# C172-XPNDR-sh_matics.net
KiCad netlist of a schematic drawn in EasyEDA
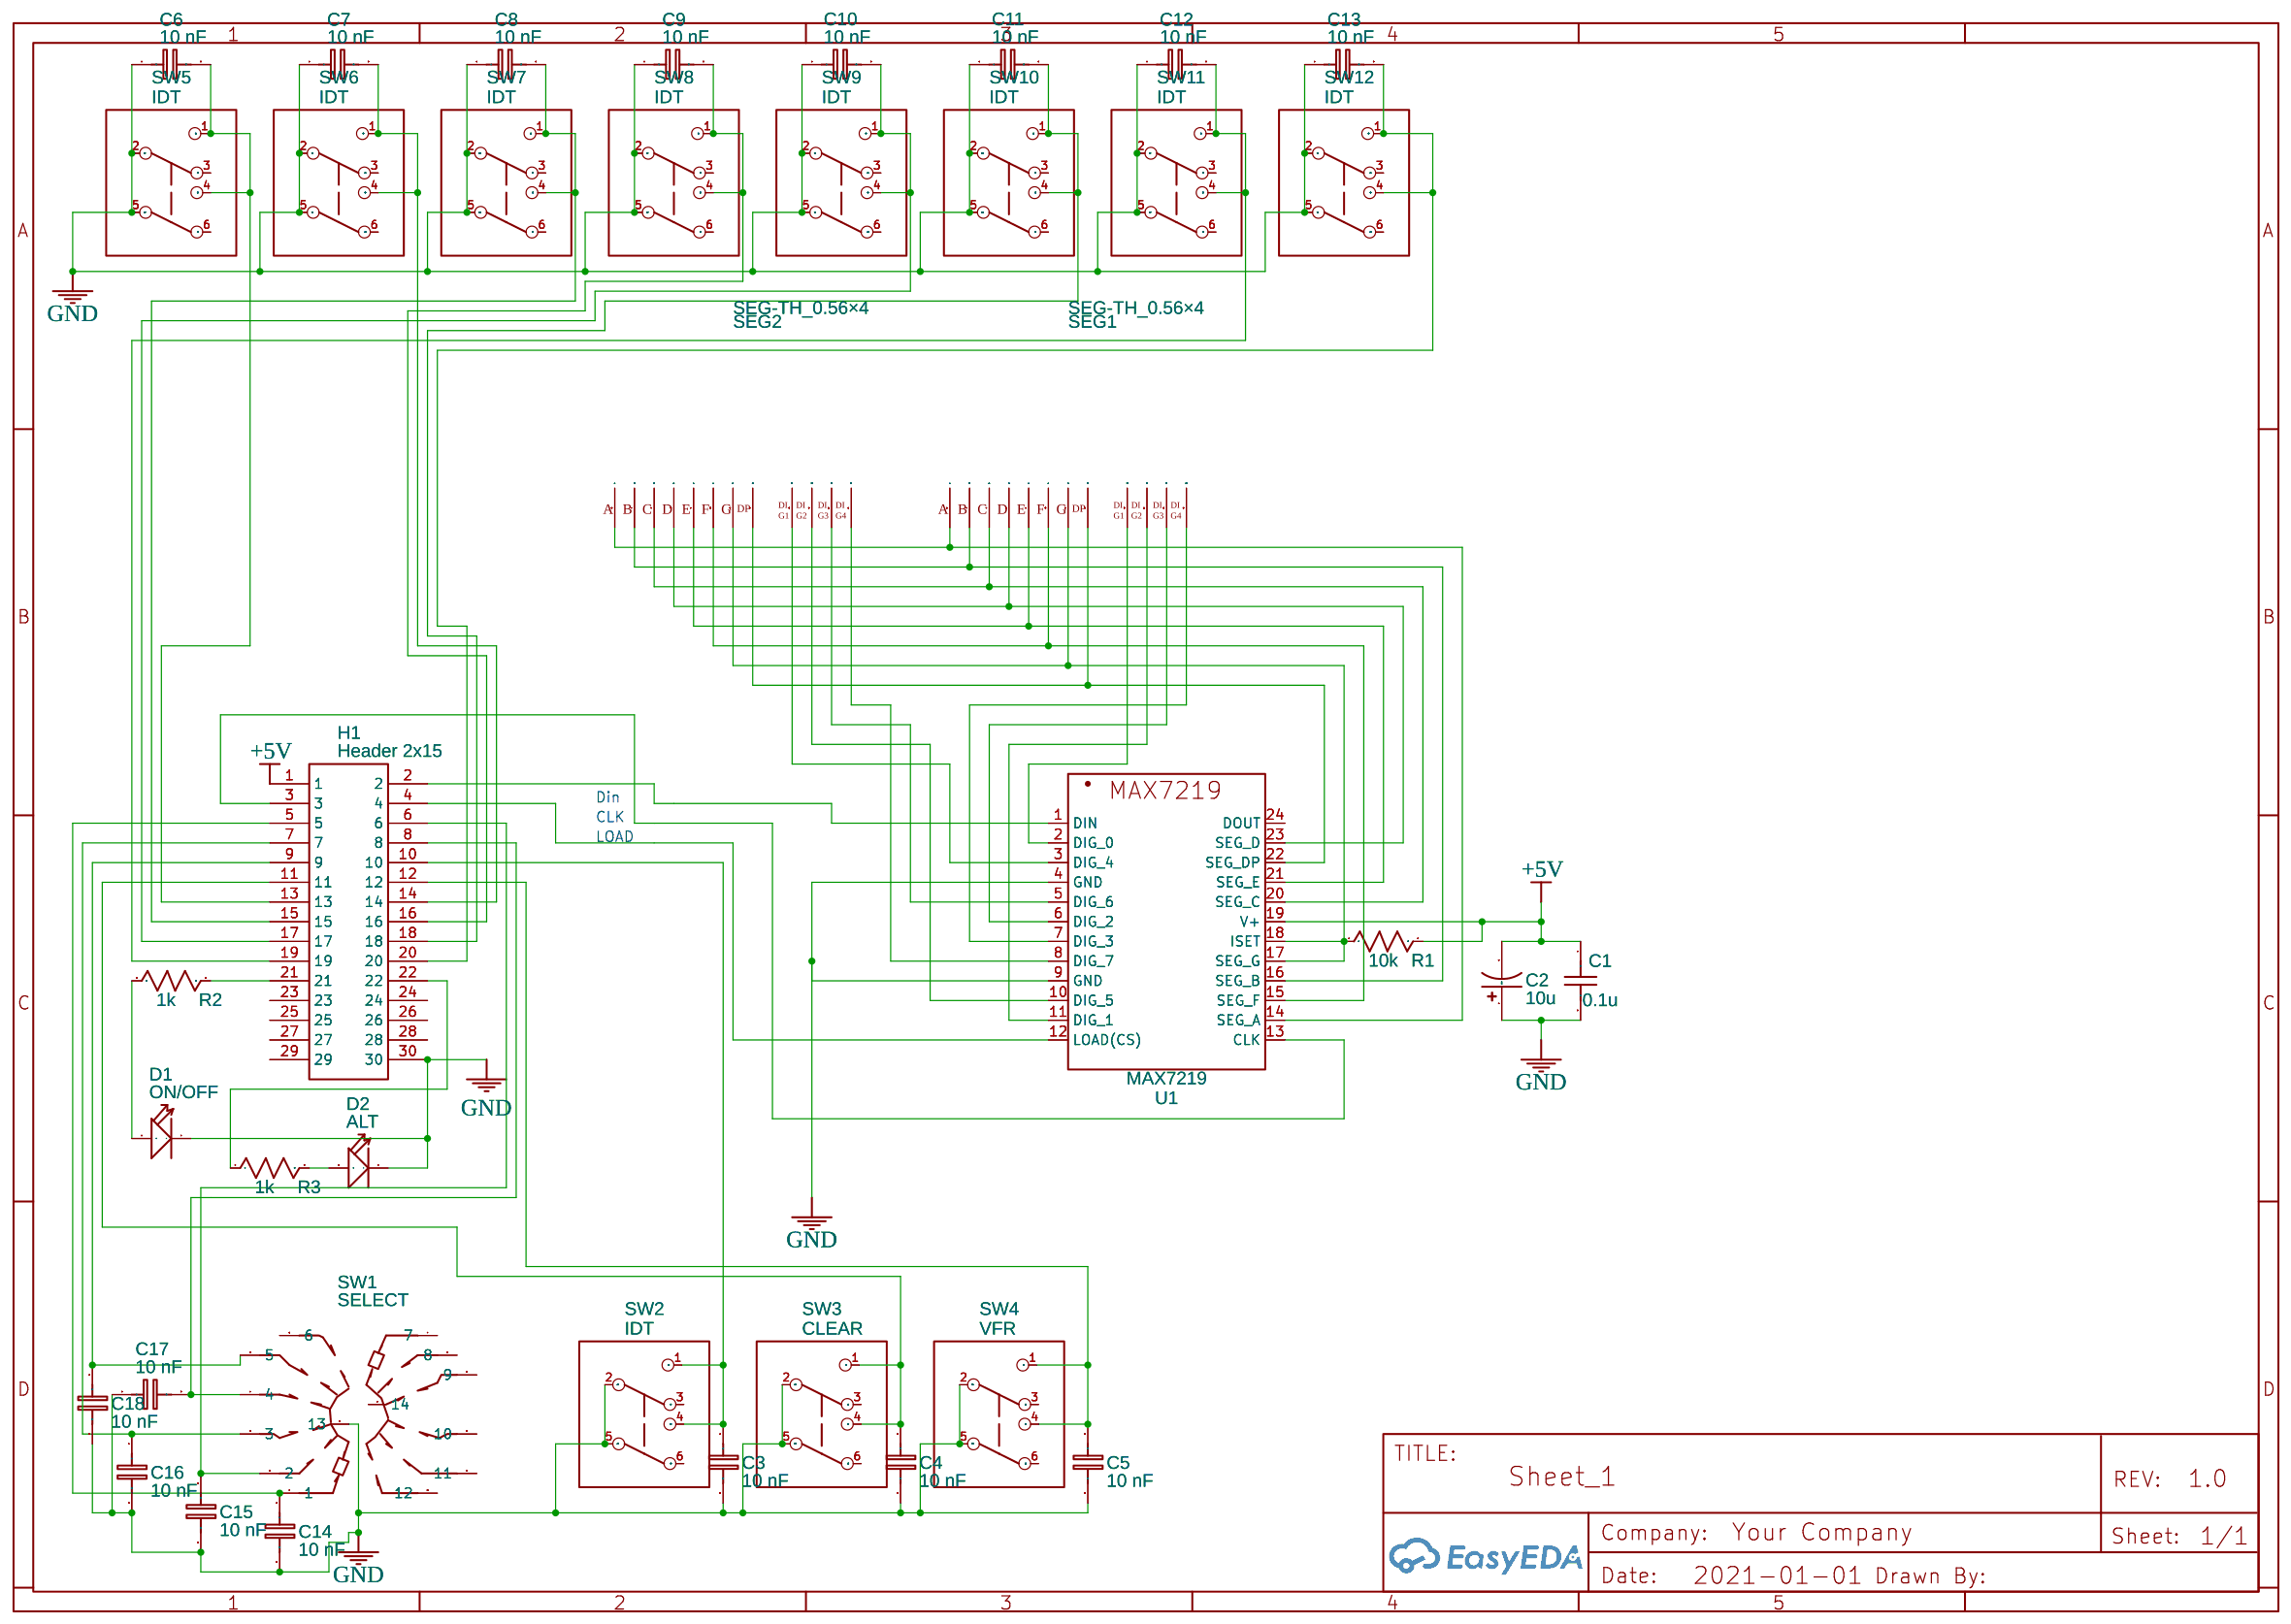
[diagram p0: schematic sheet]

(export (version "E")
  (design (tool "Eeschema 10.0.6"))
  (components
    (comp (ref "C1") (value "0.1u") (libsource (lib "") (part "C_0201_US")))
    (comp (ref "C2") (value "10u") (libsource (lib "") (part "C_Tan_SMD_A_US")))
    (comp (ref "C3") (value "10 nF") (libsource (lib "") (part "Capacitor1_EU_2")))
    (comp (ref "C4") (value "10 nF") (libsource (lib "") (part "Capacitor1_EU_2")))
    (comp (ref "C5") (value "10 nF") (libsource (lib "") (part "Capacitor1_EU_1")))
    (comp (ref "C6") (value "10 nF") (libsource (lib "") (part "Capacitor1_EU")))
    (comp (ref "C7") (value "10 nF") (libsource (lib "") (part "Capacitor1_EU_3")))
    (comp (ref "C8") (value "10 nF") (libsource (lib "") (part "Capacitor1_EU_3")))
    (comp (ref "C9") (value "10 nF") (libsource (lib "") (part "Capacitor1_EU_3")))
    (comp (ref "C10") (value "10 nF") (libsource (lib "") (part "Capacitor1_EU_3")))
    (comp (ref "C11") (value "10 nF") (libsource (lib "") (part "Capacitor1_EU_3")))
    (comp (ref "C12") (value "10 nF") (libsource (lib "") (part "Capacitor1_EU")))
    (comp (ref "C13") (value "10 nF") (libsource (lib "") (part "Capacitor1_EU")))
    (comp (ref "C14") (value "10 nF") (libsource (lib "") (part "Capacitor1_EU_1")))
    (comp (ref "C15") (value "10 nF") (libsource (lib "") (part "Capacitor1_EU_1")))
    (comp (ref "C16") (value "10 nF") (libsource (lib "") (part "Capacitor1_EU_1")))
    (comp (ref "C17") (value "10 nF") (libsource (lib "") (part "Capacitor1_EU")))
    (comp (ref "C18") (value "10 nF") (libsource (lib "") (part "Capacitor1_EU_1")))
    (comp (ref "D1")
      (value "ON/OFF")
      (fields (field (name "BOM_Manufacturer Part") "?"))
      (libsource (lib "") (part "DIP LED Red-Red;"))
    )
    (comp (ref "D2")
      (value "ALT")
      (fields (field (name "BOM_Manufacturer Part") "?"))
      (libsource (lib "") (part "DIP LED Red-Red;"))
    )
    (comp (ref "H1") (value "Header 2x15") (libsource (lib "") (part "Header 2x15")))
    (comp (ref "R1") (value "10k") (libsource (lib "") (part "R_0201_US")))
    (comp (ref "R2") (value "1k") (libsource (lib "") (part "R_0201_US")))
    (comp (ref "R3") (value "1k") (libsource (lib "") (part "R_0201_US")))
    (comp (ref "SEG1")
      (value "SEG-TH_0.56×4")
      (fields (field (name "BOM_Supplier Part") "C109200"))
      (libsource (lib "") (part "SEG-TH_0.56×4"))
    )
    (comp (ref "SEG2")
      (value "SEG-TH_0.56×4")
      (fields (field (name "BOM_Supplier Part") "C109200"))
      (libsource (lib "") (part "SEG-TH_0.56×4"))
    )
    (comp (ref "SW1")
      (value "SELECT")
      (fields (field (name "BOM_Manufacturer Part") "CK1060"))
      (libsource (lib "") (part "LORLIN  2P6T PCB SW"))
    )
    (comp (ref "SW2") (value "IDT") (libsource (lib "") (part "SW_PUSH_DPDT_MINI_7x7")))
    (comp (ref "SW3") (value "CLEAR") (libsource (lib "") (part "SW_PUSH_DPDT_MINI_7x7")))
    (comp (ref "SW4") (value "VFR") (libsource (lib "") (part "SW_PUSH_DPDT_MINI_7x7")))
    (comp (ref "SW5") (value "IDT") (libsource (lib "") (part "SW_PUSH_DPDT_MINI_7x7")))
    (comp (ref "SW6") (value "IDT") (libsource (lib "") (part "SW_PUSH_DPDT_MINI_7x7")))
    (comp (ref "SW7") (value "IDT") (libsource (lib "") (part "SW_PUSH_DPDT_MINI_7x7")))
    (comp (ref "SW8") (value "IDT") (libsource (lib "") (part "SW_PUSH_DPDT_MINI_7x7")))
    (comp (ref "SW9") (value "IDT") (libsource (lib "") (part "SW_PUSH_DPDT_MINI_7x7")))
    (comp (ref "SW10") (value "IDT") (libsource (lib "") (part "SW_PUSH_DPDT_MINI_7x7")))
    (comp (ref "SW11") (value "IDT") (libsource (lib "") (part "SW_PUSH_DPDT_MINI_7x7")))
    (comp (ref "SW12") (value "IDT") (libsource (lib "") (part "SW_PUSH_DPDT_MINI_7x7")))
    (comp (ref "U1")
      (value "MAX7219")
      (fields (field (name "BOM_Manufacturer Part") "MAXIM") (field (name "BOM_Supplier Part") "C129565"))
      (libsource (lib "") (part "MAX7219"))
    )
  )
  (nets
    (net (code "1") (name "+5V") (class "Default")
      (node (ref "C1") (pin "1") (pinfunction "1_1") (pintype "unspecified"))
      (node (ref "C2") (pin "2") (pinfunction "2_2") (pintype "unspecified"))
      (node (ref "H1") (pin "1") (pinfunction "1_1") (pintype "unspecified"))
      (node (ref "R1") (pin "2") (pinfunction "2_2") (pintype "unspecified"))
      (node (ref "U1") (pin "19") (pinfunction "V+_19") (pintype "unspecified"))
    )
    (net (code "2") (name "GND") (class "Default")
      (node (ref "C1") (pin "2") (pinfunction "2_2") (pintype "unspecified"))
      (node (ref "C10") (pin "1") (pinfunction "1_1") (pintype "unspecified"))
      (node (ref "C11") (pin "1") (pinfunction "1_1") (pintype "unspecified"))
      (node (ref "C12") (pin "1") (pinfunction "1_1") (pintype "unspecified"))
      (node (ref "C13") (pin "1") (pinfunction "1_1") (pintype "unspecified"))
      (node (ref "C14") (pin "2") (pinfunction "2_2") (pintype "unspecified"))
      (node (ref "C15") (pin "2") (pinfunction "2_2") (pintype "unspecified"))
      (node (ref "C16") (pin "2") (pinfunction "2_2") (pintype "unspecified"))
      (node (ref "C17") (pin "1") (pinfunction "1_1") (pintype "unspecified"))
      (node (ref "C18") (pin "2") (pinfunction "2_2") (pintype "unspecified"))
      (node (ref "C2") (pin "1") (pinfunction "1_1") (pintype "unspecified"))
      (node (ref "C3") (pin "2") (pinfunction "2_2") (pintype "unspecified"))
      (node (ref "C4") (pin "2") (pinfunction "2_2") (pintype "unspecified"))
      (node (ref "C5") (pin "2") (pinfunction "2_2") (pintype "unspecified"))
      (node (ref "C6") (pin "1") (pinfunction "1_1") (pintype "unspecified"))
      (node (ref "C7") (pin "1") (pinfunction "1_1") (pintype "unspecified"))
      (node (ref "C8") (pin "1") (pinfunction "1_1") (pintype "unspecified"))
      (node (ref "C9") (pin "1") (pinfunction "1_1") (pintype "unspecified"))
      (node (ref "D1") (pin "K") (pinfunction "-_K") (pintype "unspecified"))
      (node (ref "D2") (pin "K") (pinfunction "-_K") (pintype "unspecified"))
      (node (ref "H1") (pin "30") (pinfunction "30_30") (pintype "unspecified"))
      (node (ref "SW1") (pin "13") (pinfunction "13_13") (pintype "unspecified"))
      (node (ref "SW10") (pin "2") (pinfunction "COM1_2") (pintype "unspecified"))
      (node (ref "SW10") (pin "5") (pinfunction "COM2_5") (pintype "unspecified"))
      (node (ref "SW11") (pin "2") (pinfunction "COM1_2") (pintype "unspecified"))
      (node (ref "SW11") (pin "5") (pinfunction "COM2_5") (pintype "unspecified"))
      (node (ref "SW12") (pin "2") (pinfunction "COM1_2") (pintype "unspecified"))
      (node (ref "SW12") (pin "5") (pinfunction "COM2_5") (pintype "unspecified"))
      (node (ref "SW2") (pin "2") (pinfunction "COM1_2") (pintype "unspecified"))
      (node (ref "SW2") (pin "5") (pinfunction "COM2_5") (pintype "unspecified"))
      (node (ref "SW3") (pin "2") (pinfunction "COM1_2") (pintype "unspecified"))
      (node (ref "SW3") (pin "5") (pinfunction "COM2_5") (pintype "unspecified"))
      (node (ref "SW4") (pin "2") (pinfunction "COM1_2") (pintype "unspecified"))
      (node (ref "SW4") (pin "5") (pinfunction "COM2_5") (pintype "unspecified"))
      (node (ref "SW5") (pin "2") (pinfunction "COM1_2") (pintype "unspecified"))
      (node (ref "SW5") (pin "5") (pinfunction "COM2_5") (pintype "unspecified"))
      (node (ref "SW6") (pin "2") (pinfunction "COM1_2") (pintype "unspecified"))
      (node (ref "SW6") (pin "5") (pinfunction "COM2_5") (pintype "unspecified"))
      (node (ref "SW7") (pin "2") (pinfunction "COM1_2") (pintype "unspecified"))
      (node (ref "SW7") (pin "5") (pinfunction "COM2_5") (pintype "unspecified"))
      (node (ref "SW8") (pin "2") (pinfunction "COM1_2") (pintype "unspecified"))
      (node (ref "SW8") (pin "5") (pinfunction "COM2_5") (pintype "unspecified"))
      (node (ref "SW9") (pin "2") (pinfunction "COM1_2") (pintype "unspecified"))
      (node (ref "SW9") (pin "5") (pinfunction "COM2_5") (pintype "unspecified"))
      (node (ref "U1") (pin "4") (pinfunction "GND_4") (pintype "unspecified"))
      (node (ref "U1") (pin "9") (pinfunction "GND_9") (pintype "unspecified"))
    )
    (net (code "3") (name "Net-(C14-Pad1)") (class "Default")
      (node (ref "C14") (pin "1") (pinfunction "1_1") (pintype "unspecified"))
      (node (ref "H1") (pin "5") (pinfunction "5_5") (pintype "unspecified"))
      (node (ref "SW1") (pin "1") (pinfunction "1_1") (pintype "unspecified"))
    )
    (net (code "4") (name "Net-(C15-Pad1)") (class "Default")
      (node (ref "C15") (pin "1") (pinfunction "1_1") (pintype "unspecified"))
      (node (ref "H1") (pin "6") (pinfunction "6_6") (pintype "unspecified"))
      (node (ref "SW1") (pin "2") (pinfunction "2_2") (pintype "unspecified"))
    )
    (net (code "5") (name "Net-(C16-Pad1)") (class "Default")
      (node (ref "C16") (pin "1") (pinfunction "1_1") (pintype "unspecified"))
      (node (ref "H1") (pin "7") (pinfunction "7_7") (pintype "unspecified"))
      (node (ref "SW1") (pin "3") (pinfunction "3_3") (pintype "unspecified"))
    )
    (net (code "6") (name "Net-(C17-Pad2)") (class "Default")
      (node (ref "C17") (pin "2") (pinfunction "2_2") (pintype "unspecified"))
      (node (ref "H1") (pin "8") (pinfunction "8_8") (pintype "unspecified"))
      (node (ref "SW1") (pin "4") (pinfunction "4_4") (pintype "unspecified"))
    )
    (net (code "7") (name "Net-(C18-Pad1)") (class "Default")
      (node (ref "C18") (pin "1") (pinfunction "1_1") (pintype "unspecified"))
      (node (ref "H1") (pin "9") (pinfunction "9_9") (pintype "unspecified"))
      (node (ref "SW1") (pin "5") (pinfunction "5_5") (pintype "unspecified"))
    )
    (net (code "8") (name "Net-(D1-+)") (class "Default")
      (node (ref "D1") (pin "A") (pinfunction "+_A") (pintype "unspecified"))
      (node (ref "R2") (pin "1") (pinfunction "1_1") (pintype "unspecified"))
    )
    (net (code "9") (name "Net-(D2-+)") (class "Default")
      (node (ref "D2") (pin "A") (pinfunction "+_A") (pintype "unspecified"))
      (node (ref "R3") (pin "2") (pinfunction "2_2") (pintype "unspecified"))
    )
    (net (code "10") (name "Net-(H1-Pad21)") (class "Default")
      (node (ref "H1") (pin "21") (pinfunction "21_21") (pintype "unspecified"))
      (node (ref "R2") (pin "2") (pinfunction "2_2") (pintype "unspecified"))
    )
    (net (code "11") (name "Net-(H1-Pad22)") (class "Default")
      (node (ref "H1") (pin "22") (pinfunction "22_22") (pintype "unspecified"))
      (node (ref "R3") (pin "1") (pinfunction "1_1") (pintype "unspecified"))
    )
    (net (code "12") (name "Net-(SEG1-A)") (class "Default")
      (node (ref "SEG1") (pin "11") (pinfunction "A_11") (pintype "input"))
      (node (ref "SEG2") (pin "11") (pinfunction "A_11") (pintype "input"))
      (node (ref "U1") (pin "14") (pinfunction "SEG_A_14") (pintype "unspecified"))
    )
    (net (code "13") (name "Net-(SEG1-B)") (class "Default")
      (node (ref "SEG1") (pin "7") (pinfunction "B_7") (pintype "input"))
      (node (ref "SEG2") (pin "7") (pinfunction "B_7") (pintype "input"))
      (node (ref "U1") (pin "16") (pinfunction "SEG_B_16") (pintype "unspecified"))
    )
    (net (code "14") (name "Net-(SEG1-C)") (class "Default")
      (node (ref "SEG1") (pin "4") (pinfunction "C_4") (pintype "input"))
      (node (ref "SEG2") (pin "4") (pinfunction "C_4") (pintype "input"))
      (node (ref "U1") (pin "20") (pinfunction "SEG_C_20") (pintype "unspecified"))
    )
    (net (code "15") (name "Net-(SEG1-D)") (class "Default")
      (node (ref "SEG1") (pin "2") (pinfunction "D_2") (pintype "input"))
      (node (ref "SEG2") (pin "2") (pinfunction "D_2") (pintype "input"))
      (node (ref "U1") (pin "23") (pinfunction "SEG_D_23") (pintype "unspecified"))
    )
    (net (code "16") (name "Net-(SEG1-DIG1)") (class "Default")
      (node (ref "SEG1") (pin "12") (pinfunction "DIG1_12") (pintype "input"))
      (node (ref "U1") (pin "2") (pinfunction "DIG_0_2") (pintype "unspecified"))
    )
    (net (code "17") (name "Net-(SEG1-DIG2)") (class "Default")
      (node (ref "SEG1") (pin "9") (pinfunction "DIG2_9") (pintype "input"))
      (node (ref "U1") (pin "11") (pinfunction "DIG_1_11") (pintype "unspecified"))
    )
    (net (code "18") (name "Net-(SEG1-DIG3)") (class "Default")
      (node (ref "SEG1") (pin "8") (pinfunction "DIG3_8") (pintype "input"))
      (node (ref "U1") (pin "6") (pinfunction "DIG_2_6") (pintype "unspecified"))
    )
    (net (code "19") (name "Net-(SEG1-DIG4)") (class "Default")
      (node (ref "SEG1") (pin "6") (pinfunction "DIG4_6") (pintype "input"))
      (node (ref "U1") (pin "7") (pinfunction "DIG_3_7") (pintype "unspecified"))
    )
    (net (code "20") (name "Net-(SEG1-DP)") (class "Default")
      (node (ref "SEG1") (pin "3") (pinfunction "DP_3") (pintype "input"))
      (node (ref "SEG2") (pin "3") (pinfunction "DP_3") (pintype "input"))
      (node (ref "U1") (pin "22") (pinfunction "SEG_DP_22") (pintype "unspecified"))
    )
    (net (code "21") (name "Net-(SEG1-E)") (class "Default")
      (node (ref "SEG1") (pin "1") (pinfunction "E_1") (pintype "input"))
      (node (ref "SEG2") (pin "1") (pinfunction "E_1") (pintype "input"))
      (node (ref "U1") (pin "21") (pinfunction "SEG_E_21") (pintype "unspecified"))
    )
    (net (code "22") (name "Net-(SEG1-F)") (class "Default")
      (node (ref "SEG1") (pin "10") (pinfunction "F_10") (pintype "input"))
      (node (ref "SEG2") (pin "10") (pinfunction "F_10") (pintype "input"))
      (node (ref "U1") (pin "15") (pinfunction "SEG_F_15") (pintype "unspecified"))
    )
    (net (code "23") (name "Net-(SEG1-G)") (class "Default")
      (node (ref "R1") (pin "1") (pinfunction "1_1") (pintype "unspecified"))
      (node (ref "SEG1") (pin "5") (pinfunction "G_5") (pintype "input"))
      (node (ref "SEG2") (pin "5") (pinfunction "G_5") (pintype "input"))
      (node (ref "U1") (pin "17") (pinfunction "SEG_G_17") (pintype "unspecified"))
      (node (ref "U1") (pin "18") (pinfunction "ISET_18") (pintype "unspecified"))
    )
    (net (code "24") (name "Net-(SEG2-DIG1)") (class "Default")
      (node (ref "SEG2") (pin "12") (pinfunction "DIG1_12") (pintype "input"))
      (node (ref "U1") (pin "3") (pinfunction "DIG_4_3") (pintype "unspecified"))
    )
    (net (code "25") (name "Net-(SEG2-DIG2)") (class "Default")
      (node (ref "SEG2") (pin "9") (pinfunction "DIG2_9") (pintype "input"))
      (node (ref "U1") (pin "10") (pinfunction "DIG_5_10") (pintype "unspecified"))
    )
    (net (code "26") (name "Net-(SEG2-DIG3)") (class "Default")
      (node (ref "SEG2") (pin "8") (pinfunction "DIG3_8") (pintype "input"))
      (node (ref "U1") (pin "5") (pinfunction "DIG_6_5") (pintype "unspecified"))
    )
    (net (code "27") (name "Net-(SEG2-DIG4)") (class "Default")
      (node (ref "SEG2") (pin "6") (pinfunction "DIG4_6") (pintype "input"))
      (node (ref "U1") (pin "8") (pinfunction "DIG_7_8") (pintype "unspecified"))
    )
    (net (code "28") (name "Net-(SW2-NO1)") (class "Default")
      (node (ref "C3") (pin "1") (pinfunction "1_1") (pintype "unspecified"))
      (node (ref "H1") (pin "10") (pinfunction "10_10") (pintype "unspecified"))
      (node (ref "SW2") (pin "1") (pinfunction "NO1_1") (pintype "unspecified"))
      (node (ref "SW2") (pin "4") (pinfunction "NO2_4") (pintype "unspecified"))
    )
    (net (code "29") (name "Net-(SW3-NO1)") (class "Default")
      (node (ref "C4") (pin "1") (pinfunction "1_1") (pintype "unspecified"))
      (node (ref "H1") (pin "11") (pinfunction "11_11") (pintype "unspecified"))
      (node (ref "SW3") (pin "1") (pinfunction "NO1_1") (pintype "unspecified"))
      (node (ref "SW3") (pin "4") (pinfunction "NO2_4") (pintype "unspecified"))
    )
    (net (code "30") (name "Net-(SW4-NO1)") (class "Default")
      (node (ref "C5") (pin "1") (pinfunction "1_1") (pintype "unspecified"))
      (node (ref "H1") (pin "12") (pinfunction "12_12") (pintype "unspecified"))
      (node (ref "SW4") (pin "1") (pinfunction "NO1_1") (pintype "unspecified"))
      (node (ref "SW4") (pin "4") (pinfunction "NO2_4") (pintype "unspecified"))
    )
    (net (code "31") (name "Net-(SW5-NO1)") (class "Default")
      (node (ref "C6") (pin "2") (pinfunction "2_2") (pintype "unspecified"))
      (node (ref "H1") (pin "13") (pinfunction "13_13") (pintype "unspecified"))
      (node (ref "SW5") (pin "1") (pinfunction "NO1_1") (pintype "unspecified"))
      (node (ref "SW5") (pin "4") (pinfunction "NO2_4") (pintype "unspecified"))
    )
    (net (code "32") (name "Net-(SW6-NO1)") (class "Default")
      (node (ref "C7") (pin "2") (pinfunction "2_2") (pintype "unspecified"))
      (node (ref "H1") (pin "14") (pinfunction "14_14") (pintype "unspecified"))
      (node (ref "SW6") (pin "1") (pinfunction "NO1_1") (pintype "unspecified"))
      (node (ref "SW6") (pin "4") (pinfunction "NO2_4") (pintype "unspecified"))
    )
    (net (code "33") (name "Net-(SW7-NO1)") (class "Default")
      (node (ref "C8") (pin "2") (pinfunction "2_2") (pintype "unspecified"))
      (node (ref "H1") (pin "15") (pinfunction "15_15") (pintype "unspecified"))
      (node (ref "SW7") (pin "1") (pinfunction "NO1_1") (pintype "unspecified"))
      (node (ref "SW7") (pin "4") (pinfunction "NO2_4") (pintype "unspecified"))
    )
    (net (code "34") (name "Net-(SW8-NO1)") (class "Default")
      (node (ref "C9") (pin "2") (pinfunction "2_2") (pintype "unspecified"))
      (node (ref "H1") (pin "16") (pinfunction "16_16") (pintype "unspecified"))
      (node (ref "SW8") (pin "1") (pinfunction "NO1_1") (pintype "unspecified"))
      (node (ref "SW8") (pin "4") (pinfunction "NO2_4") (pintype "unspecified"))
    )
    (net (code "35") (name "Net-(SW9-NO1)") (class "Default")
      (node (ref "C10") (pin "2") (pinfunction "2_2") (pintype "unspecified"))
      (node (ref "H1") (pin "17") (pinfunction "17_17") (pintype "unspecified"))
      (node (ref "SW9") (pin "1") (pinfunction "NO1_1") (pintype "unspecified"))
      (node (ref "SW9") (pin "4") (pinfunction "NO2_4") (pintype "unspecified"))
    )
    (net (code "36") (name "Net-(SW10-NO1)") (class "Default")
      (node (ref "C11") (pin "2") (pinfunction "2_2") (pintype "unspecified"))
      (node (ref "H1") (pin "18") (pinfunction "18_18") (pintype "unspecified"))
      (node (ref "SW10") (pin "1") (pinfunction "NO1_1") (pintype "unspecified"))
      (node (ref "SW10") (pin "4") (pinfunction "NO2_4") (pintype "unspecified"))
    )
    (net (code "37") (name "Net-(SW11-NO1)") (class "Default")
      (node (ref "C12") (pin "2") (pinfunction "2_2") (pintype "unspecified"))
      (node (ref "H1") (pin "19") (pinfunction "19_19") (pintype "unspecified"))
      (node (ref "SW11") (pin "1") (pinfunction "NO1_1") (pintype "unspecified"))
      (node (ref "SW11") (pin "4") (pinfunction "NO2_4") (pintype "unspecified"))
    )
    (net (code "38") (name "Net-(SW12-NO1)") (class "Default")
      (node (ref "C13") (pin "2") (pinfunction "2_2") (pintype "unspecified"))
      (node (ref "H1") (pin "20") (pinfunction "20_20") (pintype "unspecified"))
      (node (ref "SW12") (pin "1") (pinfunction "NO1_1") (pintype "unspecified"))
      (node (ref "SW12") (pin "4") (pinfunction "NO2_4") (pintype "unspecified"))
    )
    (net (code "39") (name "Net-(U1-CLK)") (class "Default")
      (node (ref "H1") (pin "3") (pinfunction "3_3") (pintype "unspecified"))
      (node (ref "U1") (pin "13") (pinfunction "CLK_13") (pintype "unspecified"))
    )
    (net (code "40") (name "Net-(U1-DIN)") (class "Default")
      (node (ref "H1") (pin "2") (pinfunction "2_2") (pintype "unspecified"))
      (node (ref "U1") (pin "1") (pinfunction "DIN_1") (pintype "unspecified"))
    )
    (net (code "41") (name "Net-(U1-LOAD(CS))") (class "Default")
      (node (ref "H1") (pin "4") (pinfunction "4_4") (pintype "unspecified"))
      (node (ref "U1") (pin "12") (pinfunction "LOAD(CS)_12") (pintype "unspecified"))
    )
    (net (code "42") (name "unconnected-(H1-Pad23)") (class "Default")
      (node (ref "H1") (pin "23") (pinfunction "23_23") (pintype "unspecified"))
    )
    (net (code "43") (name "unconnected-(H1-Pad24)") (class "Default")
      (node (ref "H1") (pin "24") (pinfunction "24_24") (pintype "unspecified"))
    )
    (net (code "44") (name "unconnected-(H1-Pad25)") (class "Default")
      (node (ref "H1") (pin "25") (pinfunction "25_25") (pintype "unspecified"))
    )
    (net (code "45") (name "unconnected-(H1-Pad26)") (class "Default")
      (node (ref "H1") (pin "26") (pinfunction "26_26") (pintype "unspecified"))
    )
    (net (code "46") (name "unconnected-(H1-Pad27)") (class "Default")
      (node (ref "H1") (pin "27") (pinfunction "27_27") (pintype "unspecified"))
    )
    (net (code "47") (name "unconnected-(H1-Pad28)") (class "Default")
      (node (ref "H1") (pin "28") (pinfunction "28_28") (pintype "unspecified"))
    )
    (net (code "48") (name "unconnected-(H1-Pad29)") (class "Default")
      (node (ref "H1") (pin "29") (pinfunction "29_29") (pintype "unspecified"))
    )
    (net (code "49") (name "unconnected-(SW1-Pad6)") (class "Default")
      (node (ref "SW1") (pin "6") (pinfunction "6_6") (pintype "unspecified"))
    )
    (net (code "50") (name "unconnected-(SW1-Pad7)") (class "Default")
      (node (ref "SW1") (pin "7") (pinfunction "7_7") (pintype "unspecified"))
    )
    (net (code "51") (name "unconnected-(SW1-Pad8)") (class "Default")
      (node (ref "SW1") (pin "8") (pinfunction "8_8") (pintype "unspecified"))
    )
    (net (code "52") (name "unconnected-(SW1-Pad9)") (class "Default")
      (node (ref "SW1") (pin "9") (pinfunction "9_9") (pintype "unspecified"))
    )
    (net (code "53") (name "unconnected-(SW1-Pad10)") (class "Default")
      (node (ref "SW1") (pin "10") (pinfunction "10_10") (pintype "unspecified"))
    )
    (net (code "54") (name "unconnected-(SW1-Pad11)") (class "Default")
      (node (ref "SW1") (pin "11") (pinfunction "11_11") (pintype "unspecified"))
    )
    (net (code "55") (name "unconnected-(SW1-Pad12)") (class "Default")
      (node (ref "SW1") (pin "12") (pinfunction "12_12") (pintype "unspecified"))
    )
    (net (code "56") (name "unconnected-(SW1-Pad14)") (class "Default")
      (node (ref "SW1") (pin "14") (pinfunction "14_14") (pintype "unspecified"))
    )
    (net (code "57") (name "unconnected-(SW2-NC1-Pad3)") (class "Default")
      (node (ref "SW2") (pin "3") (pinfunction "NC1_3") (pintype "unspecified"))
    )
    (net (code "58") (name "unconnected-(SW2-NC2-Pad6)") (class "Default")
      (node (ref "SW2") (pin "6") (pinfunction "NC2_6") (pintype "unspecified"))
    )
    (net (code "59") (name "unconnected-(SW3-NC1-Pad3)") (class "Default")
      (node (ref "SW3") (pin "3") (pinfunction "NC1_3") (pintype "unspecified"))
    )
    (net (code "60") (name "unconnected-(SW3-NC2-Pad6)") (class "Default")
      (node (ref "SW3") (pin "6") (pinfunction "NC2_6") (pintype "unspecified"))
    )
    (net (code "61") (name "unconnected-(SW4-NC1-Pad3)") (class "Default")
      (node (ref "SW4") (pin "3") (pinfunction "NC1_3") (pintype "unspecified"))
    )
    (net (code "62") (name "unconnected-(SW4-NC2-Pad6)") (class "Default")
      (node (ref "SW4") (pin "6") (pinfunction "NC2_6") (pintype "unspecified"))
    )
    (net (code "63") (name "unconnected-(SW5-NC1-Pad3)") (class "Default")
      (node (ref "SW5") (pin "3") (pinfunction "NC1_3") (pintype "unspecified"))
    )
    (net (code "64") (name "unconnected-(SW5-NC2-Pad6)") (class "Default")
      (node (ref "SW5") (pin "6") (pinfunction "NC2_6") (pintype "unspecified"))
    )
    (net (code "65") (name "unconnected-(SW6-NC1-Pad3)") (class "Default")
      (node (ref "SW6") (pin "3") (pinfunction "NC1_3") (pintype "unspecified"))
    )
    (net (code "66") (name "unconnected-(SW6-NC2-Pad6)") (class "Default")
      (node (ref "SW6") (pin "6") (pinfunction "NC2_6") (pintype "unspecified"))
    )
    (net (code "67") (name "unconnected-(SW7-NC1-Pad3)") (class "Default")
      (node (ref "SW7") (pin "3") (pinfunction "NC1_3") (pintype "unspecified"))
    )
    (net (code "68") (name "unconnected-(SW7-NC2-Pad6)") (class "Default")
      (node (ref "SW7") (pin "6") (pinfunction "NC2_6") (pintype "unspecified"))
    )
    (net (code "69") (name "unconnected-(SW8-NC1-Pad3)") (class "Default")
      (node (ref "SW8") (pin "3") (pinfunction "NC1_3") (pintype "unspecified"))
    )
    (net (code "70") (name "unconnected-(SW8-NC2-Pad6)") (class "Default")
      (node (ref "SW8") (pin "6") (pinfunction "NC2_6") (pintype "unspecified"))
    )
    (net (code "71") (name "unconnected-(SW9-NC1-Pad3)") (class "Default")
      (node (ref "SW9") (pin "3") (pinfunction "NC1_3") (pintype "unspecified"))
    )
    (net (code "72") (name "unconnected-(SW9-NC2-Pad6)") (class "Default")
      (node (ref "SW9") (pin "6") (pinfunction "NC2_6") (pintype "unspecified"))
    )
    (net (code "73") (name "unconnected-(SW10-NC1-Pad3)") (class "Default")
      (node (ref "SW10") (pin "3") (pinfunction "NC1_3") (pintype "unspecified"))
    )
    (net (code "74") (name "unconnected-(SW10-NC2-Pad6)") (class "Default")
      (node (ref "SW10") (pin "6") (pinfunction "NC2_6") (pintype "unspecified"))
    )
    (net (code "75") (name "unconnected-(SW11-NC1-Pad3)") (class "Default")
      (node (ref "SW11") (pin "3") (pinfunction "NC1_3") (pintype "unspecified"))
    )
    (net (code "76") (name "unconnected-(SW11-NC2-Pad6)") (class "Default")
      (node (ref "SW11") (pin "6") (pinfunction "NC2_6") (pintype "unspecified"))
    )
    (net (code "77") (name "unconnected-(SW12-NC1-Pad3)") (class "Default")
      (node (ref "SW12") (pin "3") (pinfunction "NC1_3") (pintype "unspecified"))
    )
    (net (code "78") (name "unconnected-(SW12-NC2-Pad6)") (class "Default")
      (node (ref "SW12") (pin "6") (pinfunction "NC2_6") (pintype "unspecified"))
    )
    (net (code "79") (name "unconnected-(U1-DOUT-Pad24)") (class "Default")
      (node (ref "U1") (pin "24") (pinfunction "DOUT_24") (pintype "unspecified"))
    )
  )
)
